# wirelessnode.net
KiCad netlist of a schematic drawn in EAGLE
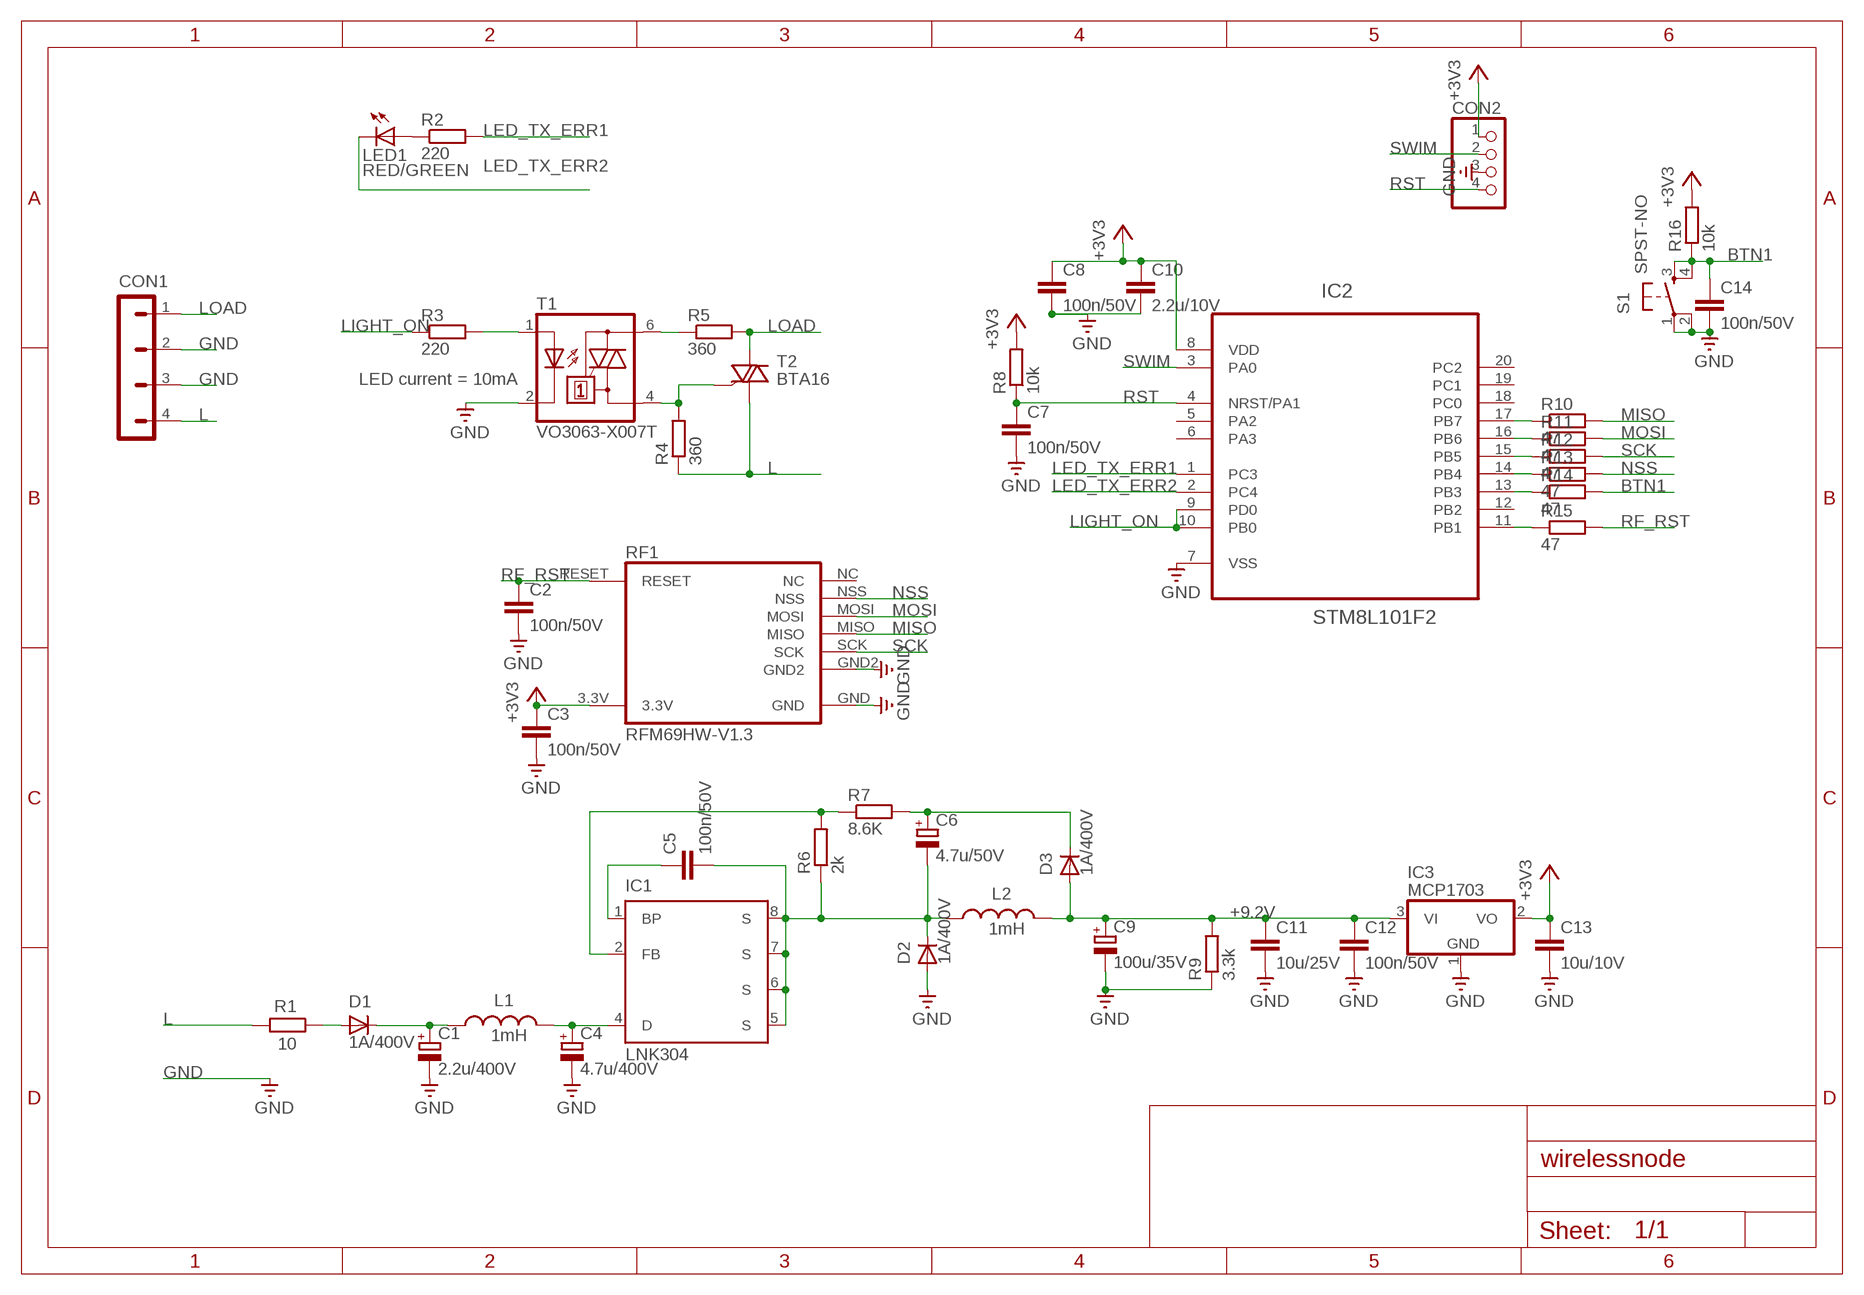
[diagram p0: schematic, sheet 1]

(export (version "E")
  (design (tool "Eeschema 10.0.6"))
  (components
    (comp (ref "C1")
      (value "2.2u/400V")
      (footprint "eagle-import:CAP_8X11.5_AIR")
      (libsource (lib "eagle-import") (part "C-POL-EUCAP_8X11.5_AIR"))
    )
    (comp (ref "C2")
      (value "100n/50V")
      (footprint "eagle-import:C0603K")
      (libsource (lib "eagle-import") (part "C-EUC0603K"))
    )
    (comp (ref "C3")
      (value "100n/50V")
      (footprint "eagle-import:C0603K")
      (libsource (lib "eagle-import") (part "C-EUC0603K"))
    )
    (comp (ref "C4")
      (value "4.7u/400V")
      (footprint "eagle-import:E5-10,5")
      (libsource (lib "eagle-import") (part "C-POL-EUE5-10,5"))
    )
    (comp (ref "C5")
      (value "100n/50V")
      (footprint "eagle-import:C0603K")
      (libsource (lib "eagle-import") (part "C-EUC0603K"))
    )
    (comp (ref "C6")
      (value "4.7u/50V")
      (footprint "eagle-import:PANASONIC_C_LARGER_PADS")
      (libsource (lib "eagle-import") (part "comp_wirelessnode_C-POL-EU"))
    )
    (comp (ref "C7")
      (value "100n/50V")
      (footprint "eagle-import:C0603K")
      (libsource (lib "eagle-import") (part "C-EUC0603K"))
    )
    (comp (ref "C8")
      (value "100n/50V")
      (footprint "eagle-import:C0603K")
      (libsource (lib "eagle-import") (part "C-EUC0603K"))
    )
    (comp (ref "C9")
      (value "100u/35V")
      (footprint "eagle-import:PANASONIC_D_LARGER_PADS")
      (libsource (lib "eagle-import") (part "comp_wirelessnode_C-POL-EUPANASONIC_D"))
    )
    (comp (ref "C10")
      (value "2.2u/10V")
      (footprint "eagle-import:C0603K")
      (libsource (lib "eagle-import") (part "C-EUC0603K"))
    )
    (comp (ref "C11")
      (value "10u/25V")
      (footprint "eagle-import:C1206")
      (libsource (lib "eagle-import") (part "C-EUC1206"))
    )
    (comp (ref "C12")
      (value "100n/50V")
      (footprint "eagle-import:C0603K")
      (libsource (lib "eagle-import") (part "C-EUC0603K"))
    )
    (comp (ref "C13")
      (value "10u/10V")
      (footprint "eagle-import:C0603K")
      (libsource (lib "eagle-import") (part "C-EUC0603K"))
    )
    (comp (ref "C14")
      (value "100n/50V")
      (footprint "eagle-import:C0603K")
      (libsource (lib "eagle-import") (part "C-EUC0603K"))
    )
    (comp (ref "CON1")
      (value "POWER_CONN_4")
      (footprint "eagle-import:TERMINAL_BLOCK_4")
      (libsource (lib "eagle-import") (part "POWER_CONN_4"))
    )
    (comp (ref "CON2")
      (value "ZL321-4P")
      (footprint "eagle-import:CON_1X4_1.27_SMD")
      (libsource (lib "eagle-import") (part "CON_1X4PIN_1.27MM_SMD"))
    )
    (comp (ref "D1")
      (value "1A/400V")
      (footprint "eagle-import:SOD-123F")
      (libsource (lib "eagle-import") (part "SL1G"))
    )
    (comp (ref "D2")
      (value "1A/400V")
      (footprint "eagle-import:DO214-AC")
      (libsource (lib "eagle-import") (part "US1G-DIO"))
    )
    (comp (ref "D3")
      (value "1A/400V")
      (footprint "eagle-import:SOD-123F")
      (libsource (lib "eagle-import") (part "SL1G"))
    )
    (comp (ref "IC1")
      (value "LNK304")
      (footprint "eagle-import:SO8_NO_PIN3")
      (libsource (lib "eagle-import") (part "LNK304"))
    )
    (comp (ref "IC2")
      (value "STM8L101F2")
      (footprint "eagle-import:TSSOP20")
      (libsource (lib "eagle-import") (part "STM8L101F2"))
    )
    (comp (ref "IC3")
      (value "MCP1703")
      (footprint "eagle-import:SOT23")
      (libsource (lib "eagle-import") (part "MCP1703CB"))
    )
    (comp (ref "L1")
      (value "1mH")
      (footprint "eagle-import:DE0703")
      (libsource (lib "eagle-import") (part "FERROCORE_DE0703-1000"))
    )
    (comp (ref "L2")
      (value "1mH")
      (footprint "eagle-import:DE0703")
      (libsource (lib "eagle-import") (part "FERROCORE_DE0703-1000"))
    )
    (comp (ref "LED1")
      (value "RED/GREEN")
      (footprint "eagle-import:LED5MM")
      (libsource (lib "eagle-import") (part "LED5MM"))
    )
    (comp (ref "R1")
      (value "10")
      (footprint "eagle-import:CF1WS")
      (libsource (lib "eagle-import") (part "R_CF1WS"))
    )
    (comp (ref "R2")
      (value "220")
      (footprint "eagle-import:R0603")
      (libsource (lib "eagle-import") (part "R-EU_R0603"))
    )
    (comp (ref "R3")
      (value "220")
      (footprint "eagle-import:R0603")
      (libsource (lib "eagle-import") (part "R-EU_R0603"))
    )
    (comp (ref "R4")
      (value "360")
      (footprint "eagle-import:R0603")
      (libsource (lib "eagle-import") (part "R-EU_R0603"))
    )
    (comp (ref "R5")
      (value "360")
      (footprint "eagle-import:R0603")
      (libsource (lib "eagle-import") (part "R-EU_R0603"))
    )
    (comp (ref "R6")
      (value "2k")
      (footprint "eagle-import:R0603")
      (libsource (lib "eagle-import") (part "R-EU_R0603"))
    )
    (comp (ref "R7")
      (value "8.6K")
      (footprint "eagle-import:R0603")
      (libsource (lib "eagle-import") (part "R-EU_R0603"))
    )
    (comp (ref "R8")
      (value "10k")
      (footprint "eagle-import:R0603")
      (libsource (lib "eagle-import") (part "R-EU_R0603"))
    )
    (comp (ref "R9")
      (value "3.3k")
      (footprint "eagle-import:R0603")
      (libsource (lib "eagle-import") (part "R-EU_R0603"))
    )
    (comp (ref "R10")
      (value "47")
      (footprint "eagle-import:R0603")
      (libsource (lib "eagle-import") (part "R-EU_R0603"))
    )
    (comp (ref "R11")
      (value "47")
      (footprint "eagle-import:R0603")
      (libsource (lib "eagle-import") (part "R-EU_R0603"))
    )
    (comp (ref "R12")
      (value "47")
      (footprint "eagle-import:R0603")
      (libsource (lib "eagle-import") (part "R-EU_R0603"))
    )
    (comp (ref "R13")
      (value "47")
      (footprint "eagle-import:R0603")
      (libsource (lib "eagle-import") (part "R-EU_R0603"))
    )
    (comp (ref "R14")
      (value "47")
      (footprint "eagle-import:R0603")
      (libsource (lib "eagle-import") (part "R-EU_R0603"))
    )
    (comp (ref "R15")
      (value "47")
      (footprint "eagle-import:R0603")
      (libsource (lib "eagle-import") (part "R-EU_R0603"))
    )
    (comp (ref "R16")
      (value "10k")
      (footprint "eagle-import:R0603")
      (libsource (lib "eagle-import") (part "R-EU_R0603"))
    )
    (comp (ref "RF1")
      (value "RFM69HW-V1.3")
      (footprint "eagle-import:RFM69HW-V1.3-SMD")
      (libsource (lib "eagle-import") (part "RFM69HW-V1.3"))
    )
    (comp (ref "S1")
      (value "SPST-NO")
      (footprint "eagle-import:DTSM-63X-V-7MM_HEIGHT")
      (libsource (lib "eagle-import") (part "DTSM-63X-V"))
    )
    (comp (ref "T1")
      (value "VO3063-X007T")
      (footprint "eagle-import:DIL6-SMD")
      (fields (field (name "MF") "FAIRCHILD SEMICONDUCTOR") (field (name "MPN") "MOC3042SM"))
      (libsource (lib "eagle-import") (part "MOC30S42"))
    )
    (comp (ref "T2")
      (value "BTA16")
      (footprint "eagle-import:TO220_SMD")
      (libsource (lib "eagle-import") (part "BT136SMD"))
    )
  )
  (nets
    (net (code "1") (name "+3V3") (class "Default")
      (node (ref "C10") (pin "1") (pinfunction "1_1") (pintype "passive"))
      (node (ref "C13") (pin "1") (pinfunction "1_1") (pintype "passive"))
      (node (ref "C3") (pin "1") (pinfunction "1_1") (pintype "passive"))
      (node (ref "C8") (pin "1") (pinfunction "1_1") (pintype "passive"))
      (node (ref "CON2") (pin "1") (pinfunction "1_1") (pintype "passive"))
      (node (ref "IC2") (pin "8") (pinfunction "VDD_8") (pintype "power_in"))
      (node (ref "IC3") (pin "2") (pinfunction "VO_2") (pintype "passive"))
      (node (ref "R16") (pin "2") (pinfunction "2_2") (pintype "passive"))
      (node (ref "R8") (pin "2") (pinfunction "2_2") (pintype "passive"))
      (node (ref "RF1") (pin "3.3V") (pinfunction "3.3V_3.3V") (pintype "power_in"))
    )
    (net (code "2") (name "/+9.2V") (class "Default")
      (node (ref "C11") (pin "1") (pinfunction "1_1") (pintype "passive"))
      (node (ref "C12") (pin "1") (pinfunction "1_1") (pintype "passive"))
      (node (ref "C9") (pin "+") (pinfunction "+_+") (pintype "passive"))
      (node (ref "D3") (pin "2") (pinfunction "A_2") (pintype "passive"))
      (node (ref "IC3") (pin "3") (pinfunction "VI_3") (pintype "input"))
      (node (ref "L2") (pin "P$2") (pinfunction "2_P$2") (pintype "passive"))
      (node (ref "R9") (pin "2") (pinfunction "2_2") (pintype "passive"))
    )
    (net (code "3") (name "/BTN1") (class "Default")
      (node (ref "C14") (pin "1") (pinfunction "1_1") (pintype "passive"))
      (node (ref "R14") (pin "2") (pinfunction "2_2") (pintype "passive"))
      (node (ref "R16") (pin "1") (pinfunction "1_1") (pintype "passive"))
      (node (ref "S1") (pin "3") (pinfunction "S_3") (pintype "passive"))
      (node (ref "S1") (pin "4") (pinfunction "S1_4") (pintype "passive"))
    )
    (net (code "4") (name "/L") (class "Default")
      (node (ref "CON1") (pin "4") (pinfunction "P$4_4") (pintype "bidirectional"))
      (node (ref "R1") (pin "2") (pinfunction "2_2") (pintype "passive"))
      (node (ref "R4") (pin "1") (pinfunction "1_1") (pintype "passive"))
      (node (ref "T2") (pin "1") (pinfunction "A1_1") (pintype "passive"))
    )
    (net (code "5") (name "/LED_TX_ERR1") (class "Default")
      (node (ref "IC2") (pin "1") (pinfunction "PC3_1") (pintype "bidirectional"))
      (node (ref "R2") (pin "2") (pinfunction "2_2") (pintype "passive"))
    )
    (net (code "6") (name "/LED_TX_ERR2") (class "Default")
      (node (ref "IC2") (pin "2") (pinfunction "PC4_2") (pintype "bidirectional"))
      (node (ref "LED1") (pin "K") (pinfunction "C_K") (pintype "passive"))
    )
    (net (code "7") (name "/LIGHT_ON") (class "Default")
      (node (ref "IC2") (pin "10") (pinfunction "PB0_10") (pintype "bidirectional"))
      (node (ref "IC2") (pin "9") (pinfunction "PD0_9") (pintype "bidirectional"))
      (node (ref "R3") (pin "1") (pinfunction "1_1") (pintype "passive"))
    )
    (net (code "8") (name "/LOAD") (class "Default")
      (node (ref "CON1") (pin "1") (pinfunction "P$1_1") (pintype "bidirectional"))
      (node (ref "R5") (pin "2") (pinfunction "2_2") (pintype "passive"))
      (node (ref "T2") (pin "2") (pinfunction "A2_2") (pintype "passive"))
    )
    (net (code "9") (name "/MISO") (class "Default")
      (node (ref "R10") (pin "2") (pinfunction "2_2") (pintype "passive"))
      (node (ref "RF1") (pin "MISO") (pinfunction "MISO_MISO") (pintype "output"))
    )
    (net (code "10") (name "/MOSI") (class "Default")
      (node (ref "R11") (pin "2") (pinfunction "2_2") (pintype "passive"))
      (node (ref "RF1") (pin "MOSI") (pinfunction "MOSI_MOSI") (pintype "output"))
    )
    (net (code "11") (name "/NSS") (class "Default")
      (node (ref "R13") (pin "2") (pinfunction "2_2") (pintype "passive"))
      (node (ref "RF1") (pin "NSS") (pinfunction "NSS_NSS") (pintype "output"))
    )
    (net (code "12") (name "/RF_RST") (class "Default")
      (node (ref "C2") (pin "1") (pinfunction "1_1") (pintype "passive"))
      (node (ref "R15") (pin "2") (pinfunction "2_2") (pintype "passive"))
      (node (ref "RF1") (pin "RESET") (pinfunction "RESET_RESET") (pintype "power_in"))
    )
    (net (code "13") (name "/RST") (class "Default")
      (node (ref "C7") (pin "1") (pinfunction "1_1") (pintype "passive"))
      (node (ref "CON2") (pin "4") (pinfunction "4_4") (pintype "passive"))
      (node (ref "IC2") (pin "4") (pinfunction "NRST/PA1_4") (pintype "bidirectional"))
      (node (ref "R8") (pin "1") (pinfunction "1_1") (pintype "passive"))
    )
    (net (code "14") (name "/SCK") (class "Default")
      (node (ref "R12") (pin "2") (pinfunction "2_2") (pintype "passive"))
      (node (ref "RF1") (pin "SCK") (pinfunction "SCK_SCK") (pintype "output"))
    )
    (net (code "15") (name "/SWIM") (class "Default")
      (node (ref "CON2") (pin "2") (pinfunction "2_2") (pintype "passive"))
      (node (ref "IC2") (pin "3") (pinfunction "PA0_3") (pintype "power_in"))
    )
    (net (code "16") (name "GND") (class "Default")
      (node (ref "C1") (pin "-") (pinfunction "-_-") (pintype "passive"))
      (node (ref "C10") (pin "2") (pinfunction "2_2") (pintype "passive"))
      (node (ref "C11") (pin "2") (pinfunction "2_2") (pintype "passive"))
      (node (ref "C12") (pin "2") (pinfunction "2_2") (pintype "passive"))
      (node (ref "C13") (pin "2") (pinfunction "2_2") (pintype "passive"))
      (node (ref "C14") (pin "2") (pinfunction "2_2") (pintype "passive"))
      (node (ref "C2") (pin "2") (pinfunction "2_2") (pintype "passive"))
      (node (ref "C3") (pin "2") (pinfunction "2_2") (pintype "passive"))
      (node (ref "C4") (pin "-") (pinfunction "-_-") (pintype "passive"))
      (node (ref "C7") (pin "2") (pinfunction "2_2") (pintype "passive"))
      (node (ref "C8") (pin "2") (pinfunction "2_2") (pintype "passive"))
      (node (ref "C9") (pin "-") (pinfunction "-_-") (pintype "passive"))
      (node (ref "CON1") (pin "2") (pinfunction "P$2_2") (pintype "bidirectional"))
      (node (ref "CON1") (pin "3") (pinfunction "P$3_3") (pintype "bidirectional"))
      (node (ref "CON2") (pin "3") (pinfunction "3_3") (pintype "passive"))
      (node (ref "D2") (pin "A") (pinfunction "A_A") (pintype "passive"))
      (node (ref "IC2") (pin "7") (pinfunction "VSS_7") (pintype "power_in"))
      (node (ref "IC3") (pin "1") (pinfunction "GND_1") (pintype "passive"))
      (node (ref "R9") (pin "1") (pinfunction "1_1") (pintype "passive"))
      (node (ref "RF1") (pin "GND") (pinfunction "GND_GND") (pintype "input"))
      (node (ref "RF1") (pin "GND2") (pinfunction "GND2_GND2") (pintype "output"))
      (node (ref "S1") (pin "1") (pinfunction "P_1") (pintype "passive"))
      (node (ref "S1") (pin "2") (pinfunction "P1_2") (pintype "passive"))
      (node (ref "T1") (pin "2") (pinfunction "C_2") (pintype "passive"))
    )
    (net (code "17") (name "Net-(D1-A)") (class "Default")
      (node (ref "D1") (pin "2") (pinfunction "A_2") (pintype "passive"))
      (node (ref "R1") (pin "1") (pinfunction "1_1") (pintype "passive"))
    )
    (net (code "18") (name "Net-(D1-C)") (class "Default")
      (node (ref "C1") (pin "+") (pinfunction "+_+") (pintype "passive"))
      (node (ref "D1") (pin "1") (pinfunction "C_1") (pintype "passive"))
      (node (ref "L1") (pin "P$1") (pinfunction "1_P$1") (pintype "passive"))
    )
    (net (code "19") (name "Net-(D3-C)") (class "Default")
      (node (ref "C6") (pin "+") (pinfunction "+_+") (pintype "passive"))
      (node (ref "D3") (pin "1") (pinfunction "C_1") (pintype "passive"))
      (node (ref "R7") (pin "2") (pinfunction "2_2") (pintype "passive"))
    )
    (net (code "20") (name "Net-(IC1-BP)") (class "Default")
      (node (ref "C5") (pin "1") (pinfunction "1_1") (pintype "passive"))
      (node (ref "IC1") (pin "1") (pinfunction "BP_1") (pintype "power_in"))
    )
    (net (code "21") (name "Net-(IC1-D)") (class "Default")
      (node (ref "C4") (pin "+") (pinfunction "+_+") (pintype "passive"))
      (node (ref "IC1") (pin "4") (pinfunction "D_4") (pintype "power_in"))
      (node (ref "L1") (pin "P$2") (pinfunction "2_P$2") (pintype "passive"))
    )
    (net (code "22") (name "Net-(IC1-FB)") (class "Default")
      (node (ref "IC1") (pin "2") (pinfunction "FB_2") (pintype "input"))
      (node (ref "R6") (pin "2") (pinfunction "2_2") (pintype "passive"))
      (node (ref "R7") (pin "1") (pinfunction "1_1") (pintype "passive"))
    )
    (net (code "23") (name "Net-(IC2-PB1)") (class "Default")
      (node (ref "IC2") (pin "11") (pinfunction "PB1_11") (pintype "bidirectional"))
      (node (ref "R15") (pin "1") (pinfunction "1_1") (pintype "passive"))
    )
    (net (code "24") (name "Net-(IC2-PB3)") (class "Default")
      (node (ref "IC2") (pin "13") (pinfunction "PB3_13") (pintype "bidirectional"))
      (node (ref "R14") (pin "1") (pinfunction "1_1") (pintype "passive"))
    )
    (net (code "25") (name "Net-(IC2-PB4)") (class "Default")
      (node (ref "IC2") (pin "14") (pinfunction "PB4_14") (pintype "bidirectional"))
      (node (ref "R13") (pin "1") (pinfunction "1_1") (pintype "passive"))
    )
    (net (code "26") (name "Net-(IC2-PB5)") (class "Default")
      (node (ref "IC2") (pin "15") (pinfunction "PB5_15") (pintype "bidirectional"))
      (node (ref "R12") (pin "1") (pinfunction "1_1") (pintype "passive"))
    )
    (net (code "27") (name "Net-(IC2-PB6)") (class "Default")
      (node (ref "IC2") (pin "16") (pinfunction "PB6_16") (pintype "bidirectional"))
      (node (ref "R11") (pin "1") (pinfunction "1_1") (pintype "passive"))
    )
    (net (code "28") (name "Net-(IC2-PB7)") (class "Default")
      (node (ref "IC2") (pin "17") (pinfunction "PB7_17") (pintype "bidirectional"))
      (node (ref "R10") (pin "1") (pinfunction "1_1") (pintype "passive"))
    )
    (net (code "29") (name "Net-(L2-1)") (class "Default")
      (node (ref "C5") (pin "2") (pinfunction "2_2") (pintype "passive"))
      (node (ref "C6") (pin "-") (pinfunction "-_-") (pintype "passive"))
      (node (ref "D2") (pin "C") (pinfunction "C_C") (pintype "passive"))
      (node (ref "IC1") (pin "5") (pinfunction "S_5") (pintype "power_in"))
      (node (ref "IC1") (pin "6") (pinfunction "S_6") (pintype "power_in"))
      (node (ref "IC1") (pin "7") (pinfunction "S_7") (pintype "power_in"))
      (node (ref "IC1") (pin "8") (pinfunction "S_8") (pintype "power_in"))
      (node (ref "L2") (pin "P$1") (pinfunction "1_P$1") (pintype "passive"))
      (node (ref "R6") (pin "1") (pinfunction "1_1") (pintype "passive"))
    )
    (net (code "30") (name "Net-(LED1-PadA)") (class "Default")
      (node (ref "LED1") (pin "A") (pinfunction "A_A") (pintype "passive"))
      (node (ref "R2") (pin "1") (pinfunction "1_1") (pintype "passive"))
    )
    (net (code "31") (name "Net-(T1-A)") (class "Default")
      (node (ref "R3") (pin "2") (pinfunction "2_2") (pintype "passive"))
      (node (ref "T1") (pin "1") (pinfunction "A_1") (pintype "passive"))
    )
    (net (code "32") (name "Net-(T1-A1)") (class "Default")
      (node (ref "R4") (pin "2") (pinfunction "2_2") (pintype "passive"))
      (node (ref "T1") (pin "4") (pinfunction "A1_4") (pintype "passive"))
      (node (ref "T2") (pin "3") (pinfunction "G_3") (pintype "passive"))
    )
    (net (code "33") (name "Net-(T1-A2)") (class "Default")
      (node (ref "R5") (pin "1") (pinfunction "1_1") (pintype "passive"))
      (node (ref "T1") (pin "6") (pinfunction "A2_6") (pintype "passive"))
    )
    (net (code "34") (name "unconnected-(IC2-PA2-Pad5)") (class "Default")
      (node (ref "IC2") (pin "5") (pinfunction "PA2_5") (pintype "bidirectional"))
    )
    (net (code "35") (name "unconnected-(IC2-PA3-Pad6)") (class "Default")
      (node (ref "IC2") (pin "6") (pinfunction "PA3_6") (pintype "bidirectional"))
    )
    (net (code "36") (name "unconnected-(IC2-PB2-Pad12)") (class "Default")
      (node (ref "IC2") (pin "12") (pinfunction "PB2_12") (pintype "bidirectional"))
    )
    (net (code "37") (name "unconnected-(IC2-PC0-Pad18)") (class "Default")
      (node (ref "IC2") (pin "18") (pinfunction "PC0_18") (pintype "bidirectional"))
    )
    (net (code "38") (name "unconnected-(IC2-PC1-Pad19)") (class "Default")
      (node (ref "IC2") (pin "19") (pinfunction "PC1_19") (pintype "bidirectional"))
    )
    (net (code "39") (name "unconnected-(IC2-PC2-Pad20)") (class "Default")
      (node (ref "IC2") (pin "20") (pinfunction "PC2_20") (pintype "bidirectional"))
    )
    (net (code "40") (name "unconnected-(RF1-PadNC)") (class "Default")
      (node (ref "RF1") (pin "NC") (pinfunction "NC_NC") (pintype "output"))
    )
  )
)
